# SCH_Weather-sensor_2024-05-27.net
KiCad netlist of a schematic drawn in EasyEDA
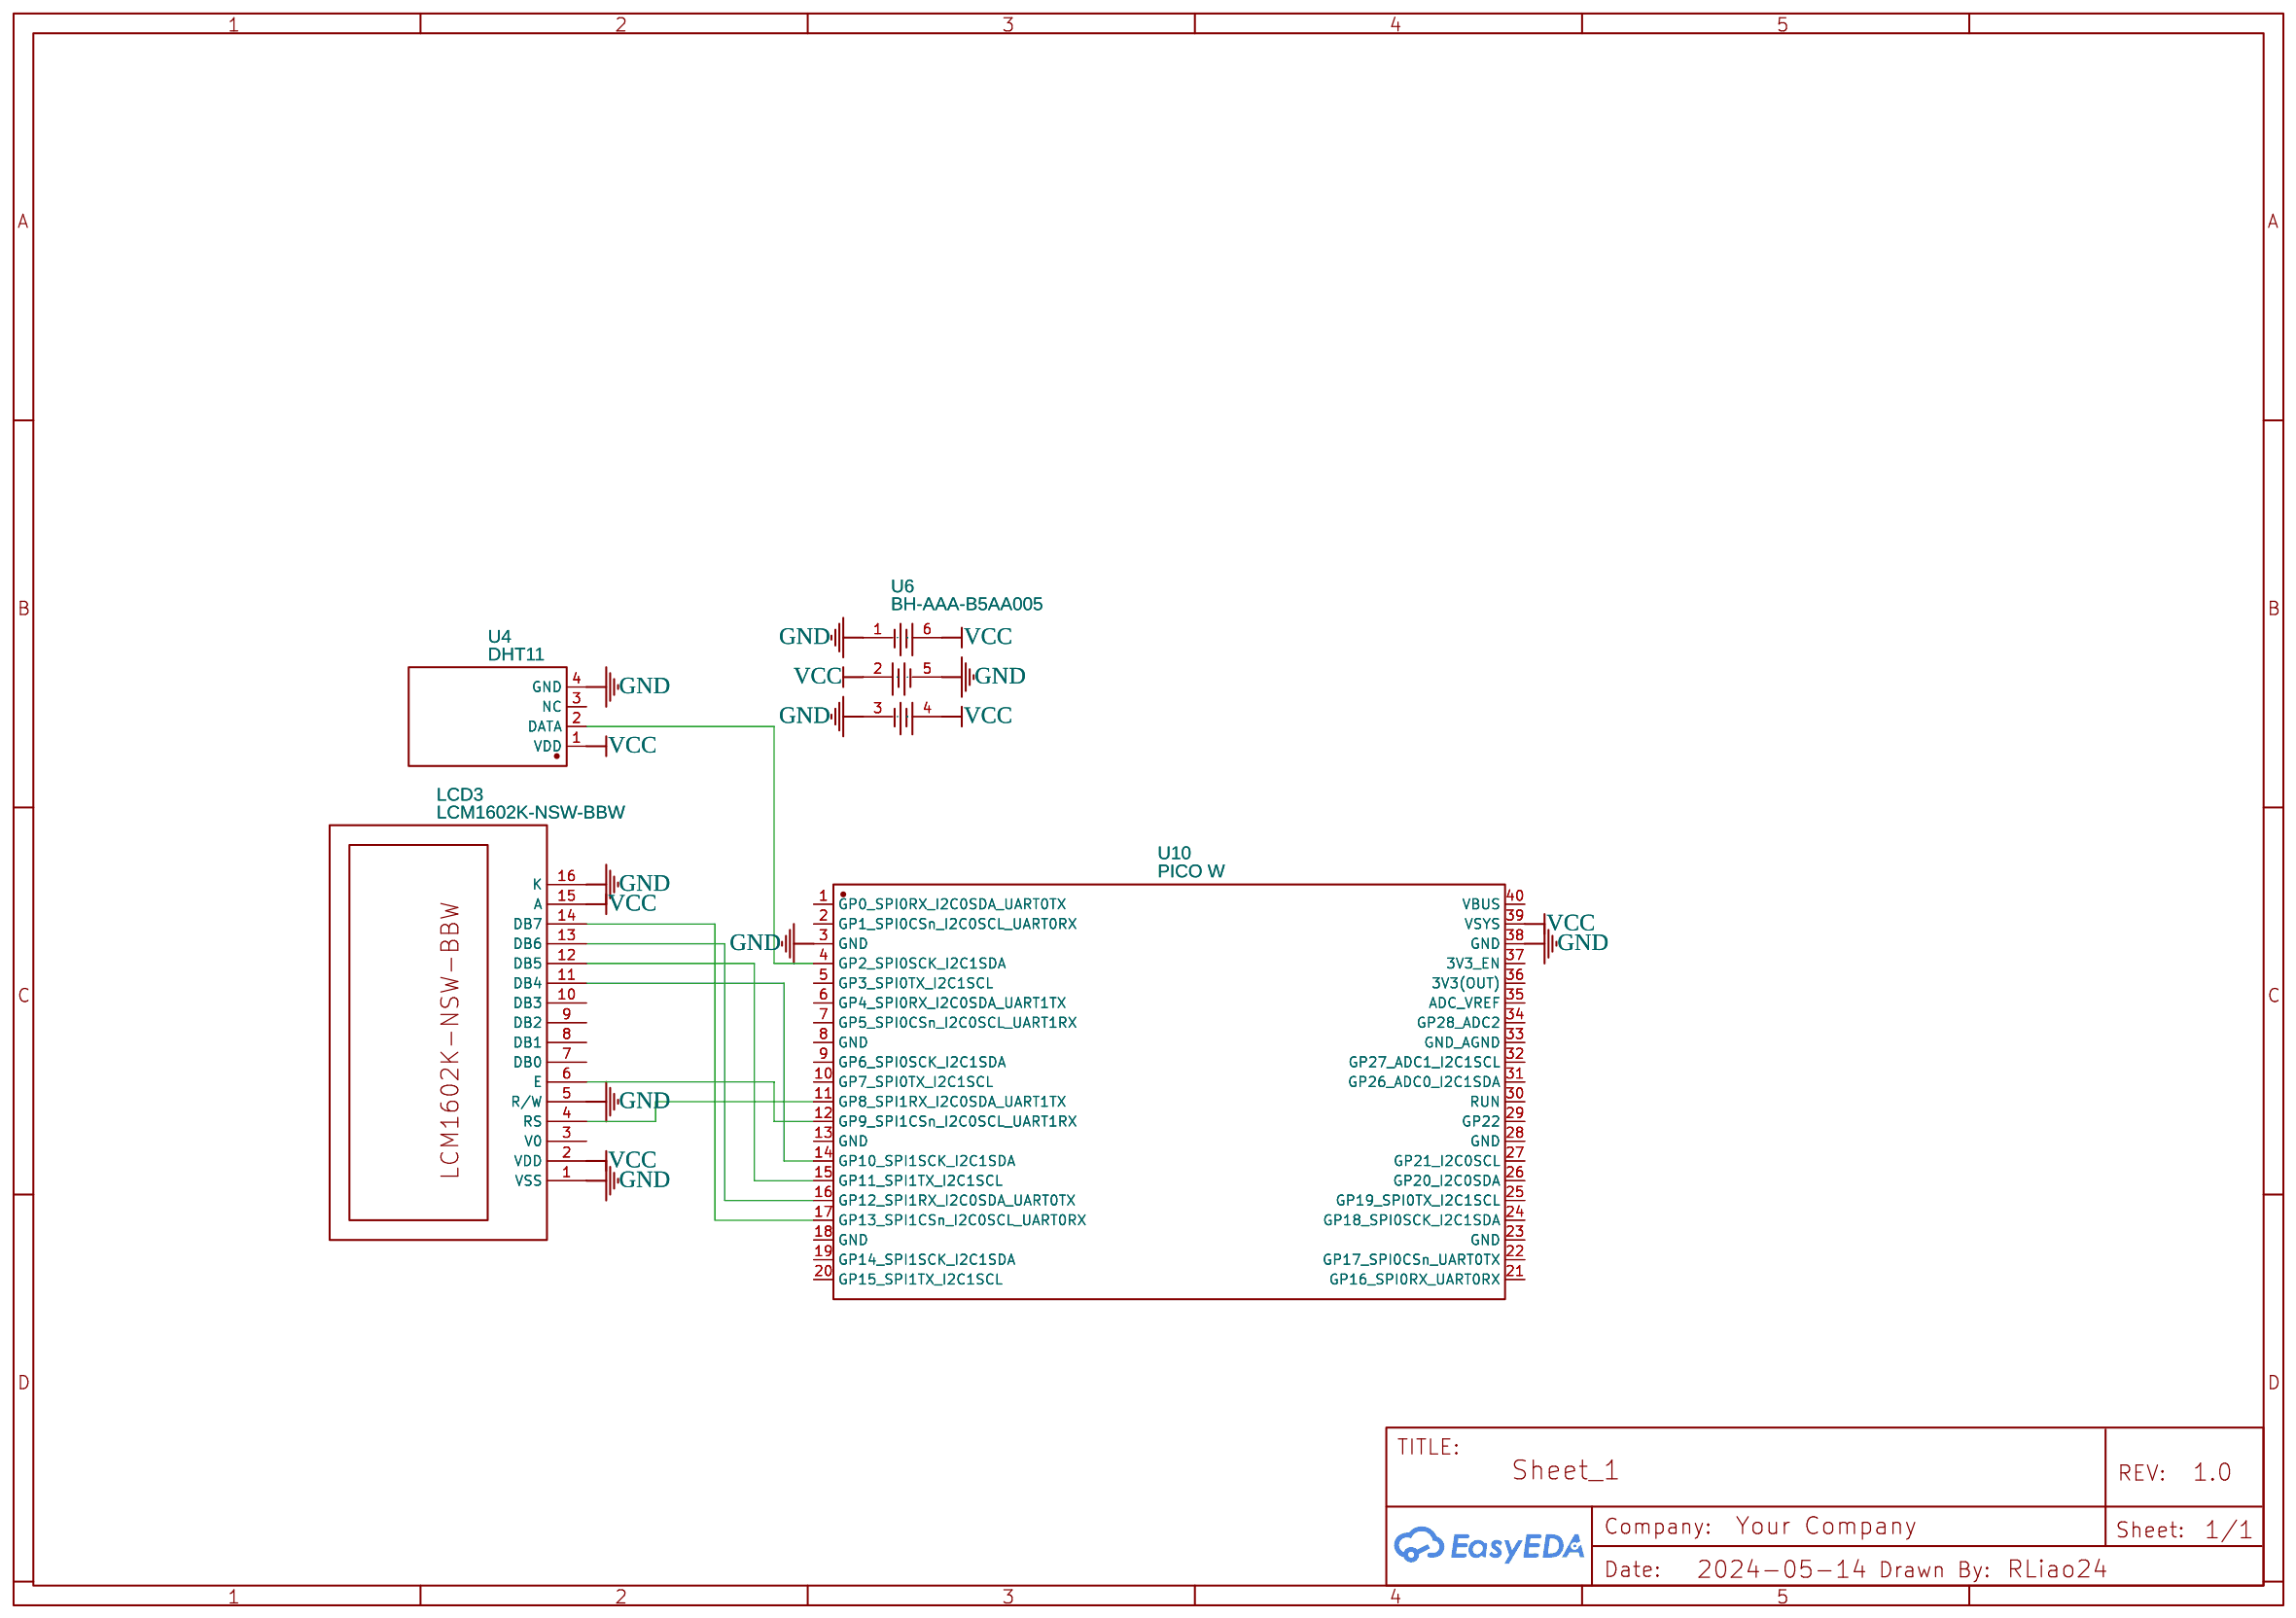
[diagram p0: schematic sheet]

(export (version "E")
  (design (tool "Eeschema 10.0.6"))
  (components
    (comp (ref "LCD3")
      (value "LCM1602K-NSW-BBW")
      (fields (field (name "Manufacturer") "LONTECH(厦门龙特)"))
      (libsource (lib "") (part "LCM1602K-NSW-BBW"))
    )
    (comp (ref "U4")
      (value "DHT11")
      (fields (field (name "Manufacturer") "广州奥松"))
      (libsource (lib "") (part "DHT11"))
    )
    (comp (ref "U6")
      (value "BH-AAA-B5AA005")
      (fields (field (name "Manufacturer") "MYOUNG(美阳)"))
      (libsource (lib "") (part "BH-AAA-B5AA005"))
    )
    (comp (ref "U10")
      (value "PICO W")
      (fields (field (name "Manufacturer") "Raspberry Pi(树莓派)"))
      (libsource (lib "") (part "PICO W"))
    )
  )
  (nets
    (net (code "1") (name "GND") (class "Default")
      (node (ref "LCD3") (pin "1") (pinfunction "VSS_1") (pintype "unspecified"))
      (node (ref "LCD3") (pin "16") (pinfunction "K_16") (pintype "unspecified"))
      (node (ref "LCD3") (pin "5") (pinfunction "R/W_5") (pintype "unspecified"))
      (node (ref "U10") (pin "3") (pinfunction "GND_3") (pintype "unspecified"))
      (node (ref "U10") (pin "38") (pinfunction "GND_38") (pintype "unspecified"))
      (node (ref "U4") (pin "4") (pinfunction "GND_4") (pintype "unspecified"))
      (node (ref "U6") (pin "1") (pinfunction "-_1") (pintype "input"))
      (node (ref "U6") (pin "3") (pinfunction "-_3") (pintype "input"))
      (node (ref "U6") (pin "5") (pinfunction "-_5") (pintype "input"))
    )
    (net (code "2") (name "Net-(LCD3-DB4)") (class "Default")
      (node (ref "LCD3") (pin "11") (pinfunction "DB4_11") (pintype "unspecified"))
      (node (ref "U10") (pin "14") (pinfunction "GP10_SPI1SCK_I2C1SDA_14") (pintype "unspecified"))
    )
    (net (code "3") (name "Net-(LCD3-DB5)") (class "Default")
      (node (ref "LCD3") (pin "12") (pinfunction "DB5_12") (pintype "unspecified"))
      (node (ref "U10") (pin "15") (pinfunction "GP11_SPI1TX_I2C1SCL_15") (pintype "unspecified"))
    )
    (net (code "4") (name "Net-(LCD3-DB6)") (class "Default")
      (node (ref "LCD3") (pin "13") (pinfunction "DB6_13") (pintype "unspecified"))
      (node (ref "U10") (pin "16") (pinfunction "GP12_SPI1RX_I2C0SDA_UART0TX_16") (pintype "unspecified"))
    )
    (net (code "5") (name "Net-(LCD3-DB7)") (class "Default")
      (node (ref "LCD3") (pin "14") (pinfunction "DB7_14") (pintype "unspecified"))
      (node (ref "U10") (pin "17") (pinfunction "GP13_SPI1CSn_I2C0SCL_UART0RX_17") (pintype "unspecified"))
    )
    (net (code "6") (name "Net-(LCD3-E)") (class "Default")
      (node (ref "LCD3") (pin "6") (pinfunction "E_6") (pintype "unspecified"))
      (node (ref "U10") (pin "12") (pinfunction "GP9_SPI1CSn_I2C0SCL_UART1RX_12") (pintype "unspecified"))
    )
    (net (code "7") (name "Net-(LCD3-RS)") (class "Default")
      (node (ref "LCD3") (pin "4") (pinfunction "RS_4") (pintype "unspecified"))
      (node (ref "U10") (pin "11") (pinfunction "GP8_SPI1RX_I2C0SDA_UART1TX_11") (pintype "unspecified"))
    )
    (net (code "8") (name "Net-(U10-GP2_SPI0SCK_I2C1SDA)") (class "Default")
      (node (ref "U10") (pin "4") (pinfunction "GP2_SPI0SCK_I2C1SDA_4") (pintype "unspecified"))
      (node (ref "U4") (pin "2") (pinfunction "DATA_2") (pintype "unspecified"))
    )
    (net (code "9") (name "VCC") (class "Default")
      (node (ref "LCD3") (pin "15") (pinfunction "A_15") (pintype "unspecified"))
      (node (ref "LCD3") (pin "2") (pinfunction "VDD_2") (pintype "unspecified"))
      (node (ref "U10") (pin "39") (pinfunction "VSYS_39") (pintype "unspecified"))
      (node (ref "U4") (pin "1") (pinfunction "VDD_1") (pintype "unspecified"))
      (node (ref "U6") (pin "2") (pinfunction "+_2") (pintype "input"))
      (node (ref "U6") (pin "4") (pinfunction "+_4") (pintype "input"))
      (node (ref "U6") (pin "6") (pinfunction "+_6") (pintype "input"))
    )
    (net (code "10") (name "unconnected-(LCD3-DB0-Pad7)") (class "Default")
      (node (ref "LCD3") (pin "7") (pinfunction "DB0_7") (pintype "unspecified"))
    )
    (net (code "11") (name "unconnected-(LCD3-DB1-Pad8)") (class "Default")
      (node (ref "LCD3") (pin "8") (pinfunction "DB1_8") (pintype "unspecified"))
    )
    (net (code "12") (name "unconnected-(LCD3-DB2-Pad9)") (class "Default")
      (node (ref "LCD3") (pin "9") (pinfunction "DB2_9") (pintype "unspecified"))
    )
    (net (code "13") (name "unconnected-(LCD3-DB3-Pad10)") (class "Default")
      (node (ref "LCD3") (pin "10") (pinfunction "DB3_10") (pintype "unspecified"))
    )
    (net (code "14") (name "unconnected-(LCD3-V0-Pad3)") (class "Default")
      (node (ref "LCD3") (pin "3") (pinfunction "V0_3") (pintype "unspecified"))
    )
    (net (code "15") (name "unconnected-(U4-NC-Pad3)") (class "Default")
      (node (ref "U4") (pin "3") (pinfunction "NC_3") (pintype "unspecified"))
    )
    (net (code "16") (name "unconnected-(U10-3V3(OUT)-Pad36)") (class "Default")
      (node (ref "U10") (pin "36") (pinfunction "3V3(OUT)_36") (pintype "unspecified"))
    )
    (net (code "17") (name "unconnected-(U10-3V3_EN-Pad37)") (class "Default")
      (node (ref "U10") (pin "37") (pinfunction "3V3_EN_37") (pintype "unspecified"))
    )
    (net (code "18") (name "unconnected-(U10-ADC_VREF-Pad35)") (class "Default")
      (node (ref "U10") (pin "35") (pinfunction "ADC_VREF_35") (pintype "unspecified"))
    )
    (net (code "19") (name "unconnected-(U10-GND-Pad8)") (class "Default")
      (node (ref "U10") (pin "8") (pinfunction "GND_8") (pintype "unspecified"))
    )
    (net (code "20") (name "unconnected-(U10-GND-Pad13)") (class "Default")
      (node (ref "U10") (pin "13") (pinfunction "GND_13") (pintype "unspecified"))
    )
    (net (code "21") (name "unconnected-(U10-GND-Pad18)") (class "Default")
      (node (ref "U10") (pin "18") (pinfunction "GND_18") (pintype "unspecified"))
    )
    (net (code "22") (name "unconnected-(U10-GND-Pad23)") (class "Default")
      (node (ref "U10") (pin "23") (pinfunction "GND_23") (pintype "unspecified"))
    )
    (net (code "23") (name "unconnected-(U10-GND-Pad28)") (class "Default")
      (node (ref "U10") (pin "28") (pinfunction "GND_28") (pintype "unspecified"))
    )
    (net (code "24") (name "unconnected-(U10-GND_AGND-Pad33)") (class "Default")
      (node (ref "U10") (pin "33") (pinfunction "GND_AGND_33") (pintype "unspecified"))
    )
    (net (code "25") (name "unconnected-(U10-GP0_SPI0RX_I2C0SDA_UART0TX-Pad1)") (class "Default")
      (node (ref "U10") (pin "1") (pinfunction "GP0_SPI0RX_I2C0SDA_UART0TX_1") (pintype "unspecified"))
    )
    (net (code "26") (name "unconnected-(U10-GP1_SPI0CSn_I2C0SCL_UART0RX-Pad2)") (class "Default")
      (node (ref "U10") (pin "2") (pinfunction "GP1_SPI0CSn_I2C0SCL_UART0RX_2") (pintype "unspecified"))
    )
    (net (code "27") (name "unconnected-(U10-GP3_SPI0TX_I2C1SCL-Pad5)") (class "Default")
      (node (ref "U10") (pin "5") (pinfunction "GP3_SPI0TX_I2C1SCL_5") (pintype "unspecified"))
    )
    (net (code "28") (name "unconnected-(U10-GP4_SPI0RX_I2C0SDA_UART1TX-Pad6)") (class "Default")
      (node (ref "U10") (pin "6") (pinfunction "GP4_SPI0RX_I2C0SDA_UART1TX_6") (pintype "unspecified"))
    )
    (net (code "29") (name "unconnected-(U10-GP5_SPI0CSn_I2C0SCL_UART1RX-Pad7)") (class "Default")
      (node (ref "U10") (pin "7") (pinfunction "GP5_SPI0CSn_I2C0SCL_UART1RX_7") (pintype "unspecified"))
    )
    (net (code "30") (name "unconnected-(U10-GP6_SPI0SCK_I2C1SDA-Pad9)") (class "Default")
      (node (ref "U10") (pin "9") (pinfunction "GP6_SPI0SCK_I2C1SDA_9") (pintype "unspecified"))
    )
    (net (code "31") (name "unconnected-(U10-GP7_SPI0TX_I2C1SCL-Pad10)") (class "Default")
      (node (ref "U10") (pin "10") (pinfunction "GP7_SPI0TX_I2C1SCL_10") (pintype "unspecified"))
    )
    (net (code "32") (name "unconnected-(U10-GP14_SPI1SCK_I2C1SDA-Pad19)") (class "Default")
      (node (ref "U10") (pin "19") (pinfunction "GP14_SPI1SCK_I2C1SDA_19") (pintype "unspecified"))
    )
    (net (code "33") (name "unconnected-(U10-GP15_SPI1TX_I2C1SCL-Pad20)") (class "Default")
      (node (ref "U10") (pin "20") (pinfunction "GP15_SPI1TX_I2C1SCL_20") (pintype "unspecified"))
    )
    (net (code "34") (name "unconnected-(U10-GP16_SPI0RX_UART0RX-Pad21)") (class "Default")
      (node (ref "U10") (pin "21") (pinfunction "GP16_SPI0RX_UART0RX_21") (pintype "unspecified"))
    )
    (net (code "35") (name "unconnected-(U10-GP17_SPI0CSn_UART0TX-Pad22)") (class "Default")
      (node (ref "U10") (pin "22") (pinfunction "GP17_SPI0CSn_UART0TX_22") (pintype "unspecified"))
    )
    (net (code "36") (name "unconnected-(U10-GP18_SPI0SCK_I2C1SDA-Pad24)") (class "Default")
      (node (ref "U10") (pin "24") (pinfunction "GP18_SPI0SCK_I2C1SDA_24") (pintype "unspecified"))
    )
    (net (code "37") (name "unconnected-(U10-GP19_SPI0TX_I2C1SCL-Pad25)") (class "Default")
      (node (ref "U10") (pin "25") (pinfunction "GP19_SPI0TX_I2C1SCL_25") (pintype "unspecified"))
    )
    (net (code "38") (name "unconnected-(U10-GP20_I2C0SDA-Pad26)") (class "Default")
      (node (ref "U10") (pin "26") (pinfunction "GP20_I2C0SDA_26") (pintype "unspecified"))
    )
    (net (code "39") (name "unconnected-(U10-GP21_I2C0SCL-Pad27)") (class "Default")
      (node (ref "U10") (pin "27") (pinfunction "GP21_I2C0SCL_27") (pintype "unspecified"))
    )
    (net (code "40") (name "unconnected-(U10-GP22-Pad29)") (class "Default")
      (node (ref "U10") (pin "29") (pinfunction "GP22_29") (pintype "unspecified"))
    )
    (net (code "41") (name "unconnected-(U10-GP26_ADC0_I2C1SDA-Pad31)") (class "Default")
      (node (ref "U10") (pin "31") (pinfunction "GP26_ADC0_I2C1SDA_31") (pintype "unspecified"))
    )
    (net (code "42") (name "unconnected-(U10-GP27_ADC1_I2C1SCL-Pad32)") (class "Default")
      (node (ref "U10") (pin "32") (pinfunction "GP27_ADC1_I2C1SCL_32") (pintype "unspecified"))
    )
    (net (code "43") (name "unconnected-(U10-GP28_ADC2-Pad34)") (class "Default")
      (node (ref "U10") (pin "34") (pinfunction "GP28_ADC2_34") (pintype "unspecified"))
    )
    (net (code "44") (name "unconnected-(U10-RUN-Pad30)") (class "Default")
      (node (ref "U10") (pin "30") (pinfunction "RUN_30") (pintype "unspecified"))
    )
    (net (code "45") (name "unconnected-(U10-VBUS-Pad40)") (class "Default")
      (node (ref "U10") (pin "40") (pinfunction "VBUS_40") (pintype "unspecified"))
    )
  )
)
